# full_board_v1.net
KiCad netlist of a schematic drawn in EAGLE
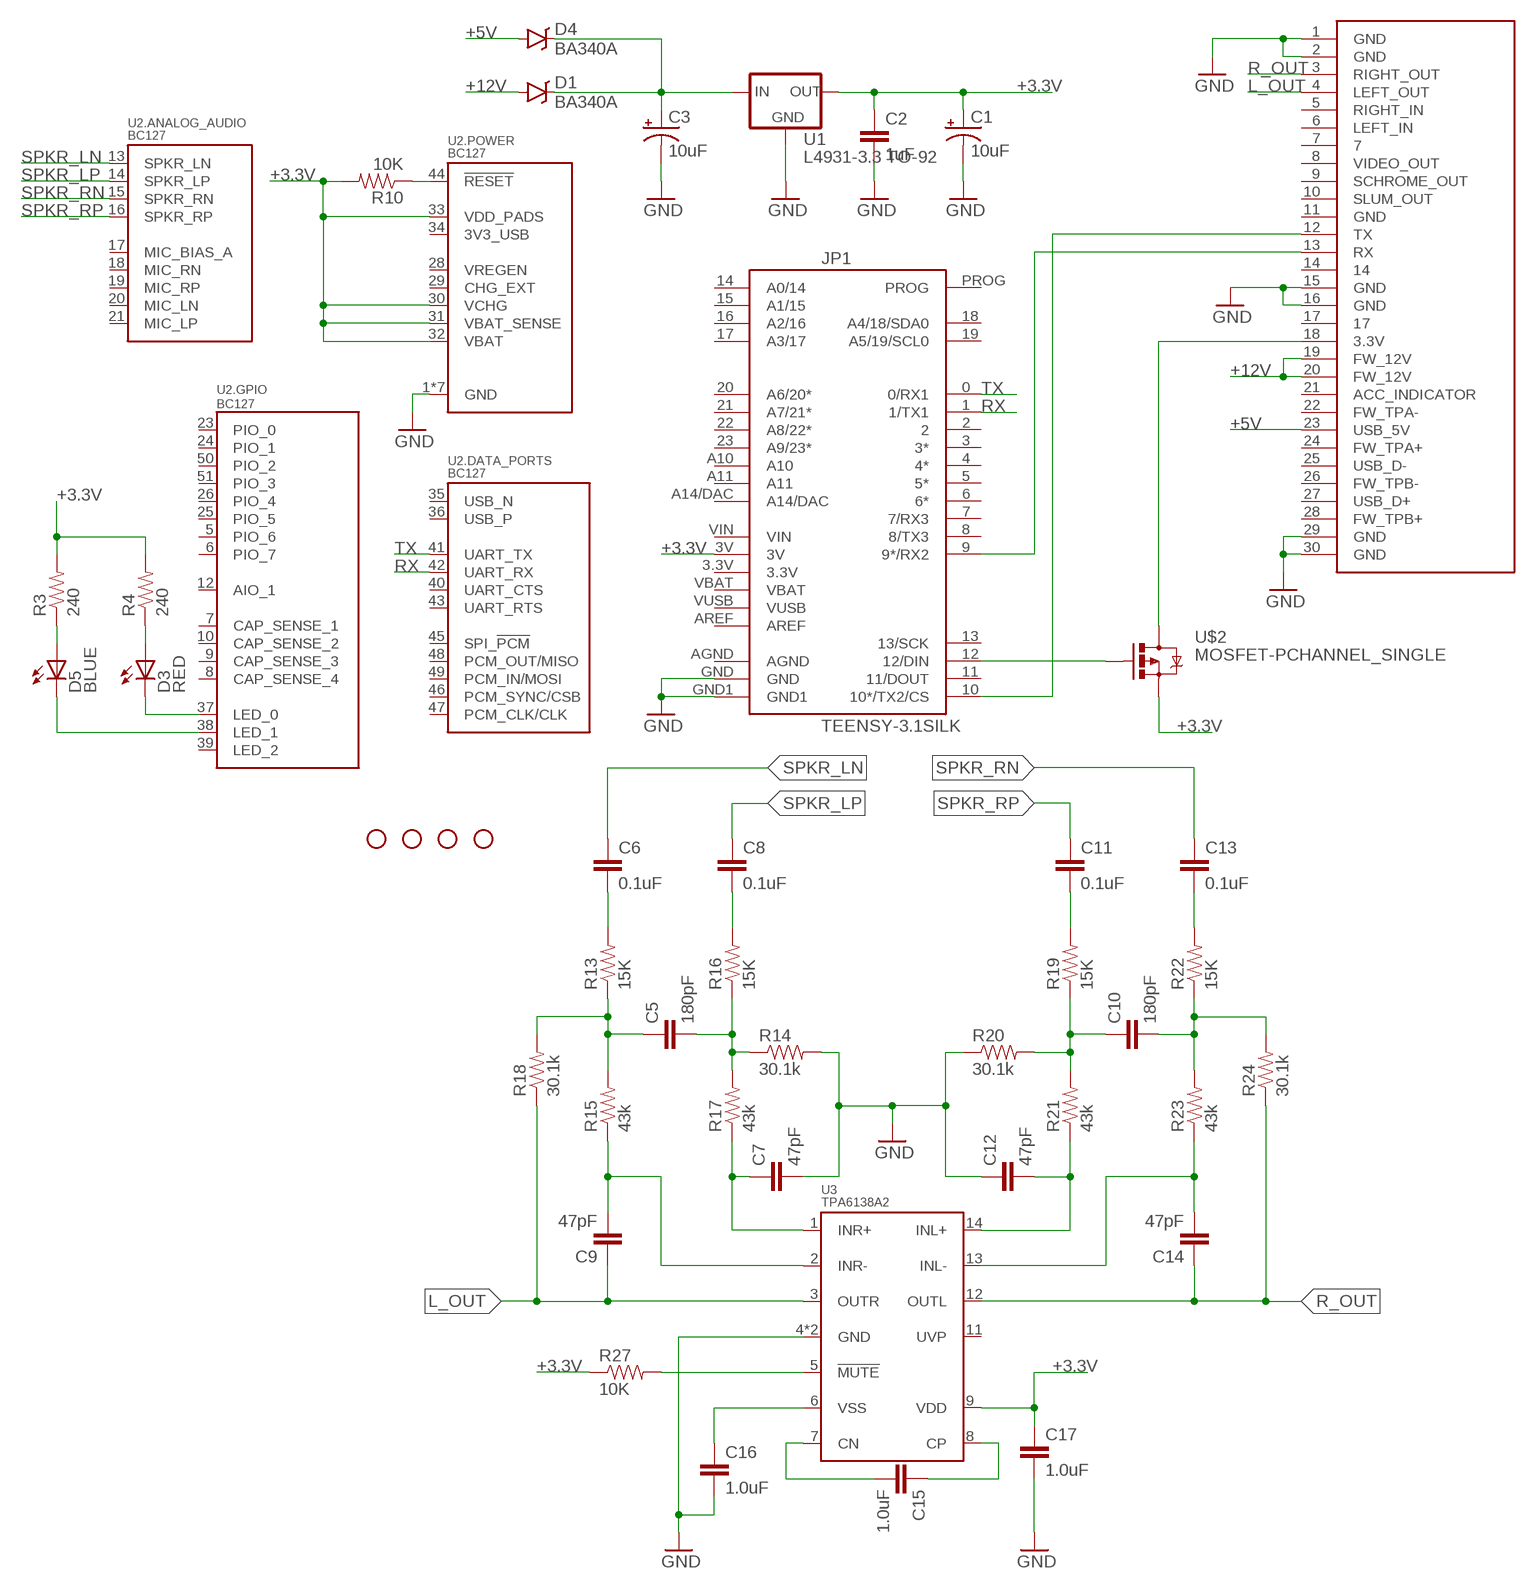
[diagram p0: schematic, sheet 1]

(export (version "E")
  (design (tool "Eeschema 10.0.6"))
  (components
    (comp (ref "C1")
      (value "10uF")
      (footprint "eagle-import:EIA3216")
      (libsource (lib "eagle-import") (part "10UF-16V-10%(TANT)"))
    )
    (comp (ref "C2")
      (value "1uF")
      (footprint "eagle-import:0805")
      (libsource (lib "eagle-import") (part "1UF-25V-10%(0805)"))
    )
    (comp (ref "C3")
      (value "10uF")
      (footprint "eagle-import:EIA3216")
      (libsource (lib "eagle-import") (part "10UF-16V-10%(TANT)"))
    )
    (comp (ref "C5")
      (value "180pF")
      (footprint "eagle-import:0603-CAP")
      (libsource (lib "eagle-import") (part "CAP0603-CAP"))
    )
    (comp (ref "C6")
      (value "0.1uF")
      (footprint "eagle-import:0603-CAP")
      (libsource (lib "eagle-import") (part "0.1UF-25V-5%(0603)"))
    )
    (comp (ref "C7")
      (value "47pF")
      (footprint "eagle-import:0603-CAP")
      (libsource (lib "eagle-import") (part "47PF-50V-5%(0603)"))
    )
    (comp (ref "C8")
      (value "0.1uF")
      (footprint "eagle-import:0603-CAP")
      (libsource (lib "eagle-import") (part "0.1UF-25V-5%(0603)"))
    )
    (comp (ref "C9")
      (value "47pF")
      (footprint "eagle-import:0603-CAP")
      (libsource (lib "eagle-import") (part "47PF-50V-5%(0603)"))
    )
    (comp (ref "C10")
      (value "180pF")
      (footprint "eagle-import:0603-CAP")
      (libsource (lib "eagle-import") (part "CAP0603-CAP"))
    )
    (comp (ref "C11")
      (value "0.1uF")
      (footprint "eagle-import:0603-CAP")
      (libsource (lib "eagle-import") (part "0.1UF-25V-5%(0603)"))
    )
    (comp (ref "C12")
      (value "47pF")
      (footprint "eagle-import:0603-CAP")
      (libsource (lib "eagle-import") (part "47PF-50V-5%(0603)"))
    )
    (comp (ref "C13")
      (value "0.1uF")
      (footprint "eagle-import:0603-CAP")
      (libsource (lib "eagle-import") (part "0.1UF-25V-5%(0603)"))
    )
    (comp (ref "C14")
      (value "47pF")
      (footprint "eagle-import:0603-CAP")
      (libsource (lib "eagle-import") (part "47PF-50V-5%(0603)"))
    )
    (comp (ref "C15")
      (value "1.0uF")
      (footprint "eagle-import:0603-CAP")
      (libsource (lib "eagle-import") (part "1.0UF-16V-10%(0603)"))
    )
    (comp (ref "C16")
      (value "1.0uF")
      (footprint "eagle-import:0603-CAP")
      (libsource (lib "eagle-import") (part "1.0UF-16V-10%(0603)"))
    )
    (comp (ref "C17")
      (value "1.0uF")
      (footprint "eagle-import:0603-CAP")
      (libsource (lib "eagle-import") (part "1.0UF-16V-10%(0603)"))
    )
    (comp (ref "D1")
      (value "BA340A")
      (footprint "eagle-import:SMA-DIODE")
      (libsource (lib "eagle-import") (part "B340A"))
    )
    (comp (ref "D3")
      (value "RED")
      (footprint "eagle-import:LED-0603")
      (libsource (lib "eagle-import") (part "LED-RED0603"))
    )
    (comp (ref "D4")
      (value "BA340A")
      (footprint "eagle-import:SMA-DIODE")
      (libsource (lib "eagle-import") (part "B340A"))
    )
    (comp (ref "D5")
      (value "BLUE")
      (footprint "eagle-import:LED-0603")
      (libsource (lib "eagle-import") (part "LED-BLUE0603"))
    )
    (comp (ref "IPOD_CONNECTOR_FEMALE")
      (value "IPOD_CONNECTOR_FEMALECUTOUT")
      (footprint "eagle-import:IPOD_FEM_SM_CUTOUTS")
      (libsource (lib "eagle-import") (part "IPOD_CONNECTOR_FEMALECUTOUT"))
    )
    (comp (ref "JP1")
      (value "TEENSY-3.1SILK")
      (footprint "eagle-import:TEENSY-3.1")
      (libsource (lib "eagle-import") (part "TEENSY-3.1SILK"))
    )
    (comp (ref "R3")
      (value "240")
      (footprint "eagle-import:0603-RES")
      (libsource (lib "eagle-import") (part "240OHM1/10W1%(0603)"))
    )
    (comp (ref "R4")
      (value "240")
      (footprint "eagle-import:0603-RES")
      (libsource (lib "eagle-import") (part "240OHM1/10W1%(0603)"))
    )
    (comp (ref "R10")
      (value "10K")
      (footprint "eagle-import:0603-RES")
      (libsource (lib "eagle-import") (part "10KOHM1/10W1%(0603)0603"))
    )
    (comp (ref "R13")
      (value "15K")
      (footprint "eagle-import:0603-RES")
      (libsource (lib "eagle-import") (part "15KOHM1/10W1%(0603)0603"))
    )
    (comp (ref "R14")
      (value "30.1k")
      (footprint "eagle-import:0603-RES")
      (libsource (lib "eagle-import") (part "30.1KOHM1/10W1%(0603)"))
    )
    (comp (ref "R15")
      (value "43k")
      (footprint "eagle-import:0603-RES")
      (libsource (lib "eagle-import") (part "43KOHM1/10W1%(0603)"))
    )
    (comp (ref "R16")
      (value "15K")
      (footprint "eagle-import:0603-RES")
      (libsource (lib "eagle-import") (part "15KOHM1/10W1%(0603)0603"))
    )
    (comp (ref "R17")
      (value "43k")
      (footprint "eagle-import:0603-RES")
      (libsource (lib "eagle-import") (part "43KOHM1/10W1%(0603)"))
    )
    (comp (ref "R18")
      (value "30.1k")
      (footprint "eagle-import:0603-RES")
      (libsource (lib "eagle-import") (part "30.1KOHM1/10W1%(0603)"))
    )
    (comp (ref "R19")
      (value "15K")
      (footprint "eagle-import:0603-RES")
      (libsource (lib "eagle-import") (part "15KOHM1/10W1%(0603)0603"))
    )
    (comp (ref "R20")
      (value "30.1k")
      (footprint "eagle-import:0603-RES")
      (libsource (lib "eagle-import") (part "30.1KOHM1/10W1%(0603)"))
    )
    (comp (ref "R21")
      (value "43k")
      (footprint "eagle-import:0603-RES")
      (libsource (lib "eagle-import") (part "43KOHM1/10W1%(0603)"))
    )
    (comp (ref "R22")
      (value "15K")
      (footprint "eagle-import:0603-RES")
      (libsource (lib "eagle-import") (part "15KOHM1/10W1%(0603)0603"))
    )
    (comp (ref "R23")
      (value "43k")
      (footprint "eagle-import:0603-RES")
      (libsource (lib "eagle-import") (part "43KOHM1/10W1%(0603)"))
    )
    (comp (ref "R24")
      (value "30.1k")
      (footprint "eagle-import:0603-RES")
      (libsource (lib "eagle-import") (part "30.1KOHM1/10W1%(0603)"))
    )
    (comp (ref "R27")
      (value "10K")
      (footprint "eagle-import:0603-RES")
      (libsource (lib "eagle-import") (part "10KOHM1/10W1%(0603)0603"))
    )
    (comp (ref "STANDOFF1")
      (value "STAND-OFF")
      (footprint "eagle-import:STAND-OFF")
      (libsource (lib "eagle-import") (part "STAND-OFF"))
    )
    (comp (ref "STANDOFF2")
      (value "STAND-OFF")
      (footprint "eagle-import:STAND-OFF")
      (libsource (lib "eagle-import") (part "STAND-OFF"))
    )
    (comp (ref "STANDOFF3")
      (value "STAND-OFF")
      (footprint "eagle-import:STAND-OFF")
      (libsource (lib "eagle-import") (part "STAND-OFF"))
    )
    (comp (ref "STANDOFF4")
      (value "STAND-OFF")
      (footprint "eagle-import:STAND-OFF")
      (libsource (lib "eagle-import") (part "STAND-OFF"))
    )
    (comp (ref "U$2")
      (value "MOSFET-PCHANNEL_SINGLE")
      (footprint "eagle-import:SOT563-SINGLEFET")
      (libsource (lib "eagle-import") (part "MOSFET-PCHANNEL_SINGLE"))
    )
    (comp (ref "U1")
      (value "L4931-3.3 TO-92")
      (footprint "eagle-import:TO-92")
      (libsource (lib "eagle-import") (part "V_REG_78XXTO-92_UNTESTED"))
    )
    (comp (ref "U2")
      (value "BC127")
      (footprint "eagle-import:BC127_XTRA_PASTE")
      (libsource (lib "eagle-import") (part "BC127EXTRA_PASTE"))
    )
    (comp (ref "U3")
      (value "TPA6138A2")
      (footprint "eagle-import:TSSOP-14")
      (libsource (lib "eagle-import") (part "TPA6138A2"))
    )
  )
  (nets
    (net (code "1") (name "/+3.3V") (class "Default")
      (node (ref "C1") (pin "A") (pinfunction "+_A") (pintype "passive"))
      (node (ref "C17") (pin "1") (pinfunction "1_1") (pintype "passive"))
      (node (ref "C2") (pin "1") (pinfunction "1_1") (pintype "passive"))
      (node (ref "JP1") (pin "3V") (pinfunction "3V_3V") (pintype "bidirectional"))
      (node (ref "R10") (pin "2") (pinfunction "2_2") (pintype "passive"))
      (node (ref "R27") (pin "1") (pinfunction "1_1") (pintype "passive"))
      (node (ref "R3") (pin "2") (pinfunction "2_2") (pintype "passive"))
      (node (ref "R4") (pin "2") (pinfunction "2_2") (pintype "passive"))
      (node (ref "U$2") (pin "S") (pinfunction "S_S") (pintype "passive"))
      (node (ref "U1") (pin "1") (pinfunction "OUT_1") (pintype "passive"))
      (node (ref "U2") (pin "30") (pinfunction "VCHG_30") (pintype "bidirectional"))
      (node (ref "U2") (pin "31") (pinfunction "VBAT_SENSE_31") (pintype "bidirectional"))
      (node (ref "U2") (pin "32") (pinfunction "VBAT_32") (pintype "bidirectional"))
      (node (ref "U2") (pin "33") (pinfunction "VDD_PADS_33") (pintype "bidirectional"))
      (node (ref "U3") (pin "9") (pinfunction "VDD_9") (pintype "bidirectional"))
    )
    (net (code "2") (name "/+5V") (class "Default")
      (node (ref "D4") (pin "A") (pinfunction "A_A") (pintype "passive"))
      (node (ref "IPOD_CONNECTOR_FEMALE") (pin "23") (pinfunction "USB_5V_23") (pintype "bidirectional"))
    )
    (net (code "3") (name "/+12V") (class "Default")
      (node (ref "D1") (pin "A") (pinfunction "A_A") (pintype "passive"))
      (node (ref "IPOD_CONNECTOR_FEMALE") (pin "19") (pinfunction "FW_12V_19") (pintype "bidirectional"))
      (node (ref "IPOD_CONNECTOR_FEMALE") (pin "20") (pinfunction "FW_12V_20") (pintype "bidirectional"))
    )
    (net (code "4") (name "/RX") (class "Default")
      (node (ref "JP1") (pin "1") (pinfunction "1/TX1_1") (pintype "bidirectional"))
      (node (ref "U2") (pin "42") (pinfunction "UART_RX_42") (pintype "bidirectional"))
    )
    (net (code "5") (name "/TX") (class "Default")
      (node (ref "JP1") (pin "0") (pinfunction "0/RX1_0") (pintype "bidirectional"))
      (node (ref "U2") (pin "41") (pinfunction "UART_TX_41") (pintype "bidirectional"))
    )
    (net (code "6") (name "GND") (class "Default")
      (node (ref "C1") (pin "C") (pinfunction "-_C") (pintype "passive"))
      (node (ref "C12") (pin "1") (pinfunction "1_1") (pintype "passive"))
      (node (ref "C16") (pin "2") (pinfunction "2_2") (pintype "passive"))
      (node (ref "C17") (pin "2") (pinfunction "2_2") (pintype "passive"))
      (node (ref "C2") (pin "2") (pinfunction "2_2") (pintype "passive"))
      (node (ref "C3") (pin "C") (pinfunction "-_C") (pintype "passive"))
      (node (ref "C7") (pin "2") (pinfunction "2_2") (pintype "passive"))
      (node (ref "IPOD_CONNECTOR_FEMALE") (pin "1") (pinfunction "GND_1") (pintype "bidirectional"))
      (node (ref "IPOD_CONNECTOR_FEMALE") (pin "15") (pinfunction "GND_15") (pintype "bidirectional"))
      (node (ref "IPOD_CONNECTOR_FEMALE") (pin "16") (pinfunction "GND_16") (pintype "bidirectional"))
      (node (ref "IPOD_CONNECTOR_FEMALE") (pin "2") (pinfunction "GND_2") (pintype "bidirectional"))
      (node (ref "IPOD_CONNECTOR_FEMALE") (pin "29") (pinfunction "GND_29") (pintype "bidirectional"))
      (node (ref "IPOD_CONNECTOR_FEMALE") (pin "30") (pinfunction "GND_30") (pintype "bidirectional"))
      (node (ref "JP1") (pin "GND") (pinfunction "GND_GND") (pintype "bidirectional"))
      (node (ref "JP1") (pin "GND1") (pinfunction "GND1_GND1") (pintype "bidirectional"))
      (node (ref "R14") (pin "2") (pinfunction "2_2") (pintype "passive"))
      (node (ref "R20") (pin "1") (pinfunction "1_1") (pintype "passive"))
      (node (ref "U1") (pin "2") (pinfunction "GND_2") (pintype "input"))
      (node (ref "U2") (pin "1") (pinfunction "GND_1") (pintype "bidirectional"))
      (node (ref "U2") (pin "11") (pinfunction "GND_11") (pintype "bidirectional"))
      (node (ref "U2") (pin "2") (pinfunction "GND_2") (pintype "bidirectional"))
      (node (ref "U2") (pin "22") (pinfunction "GND_22") (pintype "bidirectional"))
      (node (ref "U2") (pin "27") (pinfunction "GND_27") (pintype "bidirectional"))
      (node (ref "U2") (pin "3") (pinfunction "GND_3") (pintype "bidirectional"))
      (node (ref "U2") (pin "4") (pinfunction "GND_4") (pintype "bidirectional"))
      (node (ref "U3") (pin "10") (pinfunction "GND_10") (pintype "bidirectional"))
      (node (ref "U3") (pin "4") (pinfunction "GND_4") (pintype "bidirectional"))
    )
    (net (code "7") (name "L_OUT") (class "Default")
      (node (ref "C9") (pin "1") (pinfunction "1_1") (pintype "passive"))
      (node (ref "IPOD_CONNECTOR_FEMALE") (pin "4") (pinfunction "LEFT_OUT_4") (pintype "bidirectional"))
      (node (ref "R18") (pin "1") (pinfunction "1_1") (pintype "passive"))
      (node (ref "U3") (pin "3") (pinfunction "OUTR_3") (pintype "bidirectional"))
    )
    (net (code "8") (name "Net-(C3-+)") (class "Default")
      (node (ref "C3") (pin "A") (pinfunction "+_A") (pintype "passive"))
      (node (ref "D1") (pin "C") (pinfunction "C_C") (pintype "passive"))
      (node (ref "D4") (pin "C") (pinfunction "C_C") (pintype "passive"))
      (node (ref "U1") (pin "3") (pinfunction "IN_3") (pintype "input"))
    )
    (net (code "9") (name "Net-(C5-Pad1)") (class "Default")
      (node (ref "C5") (pin "1") (pinfunction "1_1") (pintype "passive"))
      (node (ref "R13") (pin "1") (pinfunction "1_1") (pintype "passive"))
      (node (ref "R15") (pin "2") (pinfunction "2_2") (pintype "passive"))
      (node (ref "R18") (pin "2") (pinfunction "2_2") (pintype "passive"))
    )
    (net (code "10") (name "Net-(C5-Pad2)") (class "Default")
      (node (ref "C5") (pin "2") (pinfunction "2_2") (pintype "passive"))
      (node (ref "R14") (pin "1") (pinfunction "1_1") (pintype "passive"))
      (node (ref "R16") (pin "1") (pinfunction "1_1") (pintype "passive"))
      (node (ref "R17") (pin "2") (pinfunction "2_2") (pintype "passive"))
    )
    (net (code "11") (name "Net-(C6-Pad2)") (class "Default")
      (node (ref "C6") (pin "2") (pinfunction "2_2") (pintype "passive"))
      (node (ref "R13") (pin "2") (pinfunction "2_2") (pintype "passive"))
    )
    (net (code "12") (name "Net-(C8-Pad2)") (class "Default")
      (node (ref "C8") (pin "2") (pinfunction "2_2") (pintype "passive"))
      (node (ref "R16") (pin "2") (pinfunction "2_2") (pintype "passive"))
    )
    (net (code "13") (name "Net-(C10-Pad1)") (class "Default")
      (node (ref "C10") (pin "1") (pinfunction "1_1") (pintype "passive"))
      (node (ref "R19") (pin "1") (pinfunction "1_1") (pintype "passive"))
      (node (ref "R20") (pin "2") (pinfunction "2_2") (pintype "passive"))
      (node (ref "R21") (pin "2") (pinfunction "2_2") (pintype "passive"))
    )
    (net (code "14") (name "Net-(C10-Pad2)") (class "Default")
      (node (ref "C10") (pin "2") (pinfunction "2_2") (pintype "passive"))
      (node (ref "R22") (pin "1") (pinfunction "1_1") (pintype "passive"))
      (node (ref "R23") (pin "2") (pinfunction "2_2") (pintype "passive"))
      (node (ref "R24") (pin "2") (pinfunction "2_2") (pintype "passive"))
    )
    (net (code "15") (name "Net-(C11-Pad2)") (class "Default")
      (node (ref "C11") (pin "2") (pinfunction "2_2") (pintype "passive"))
      (node (ref "R19") (pin "2") (pinfunction "2_2") (pintype "passive"))
    )
    (net (code "16") (name "Net-(C13-Pad2)") (class "Default")
      (node (ref "C13") (pin "2") (pinfunction "2_2") (pintype "passive"))
      (node (ref "R22") (pin "2") (pinfunction "2_2") (pintype "passive"))
    )
    (net (code "17") (name "Net-(D3-PadA)") (class "Default")
      (node (ref "D3") (pin "A") (pinfunction "A_A") (pintype "passive"))
      (node (ref "R4") (pin "1") (pinfunction "1_1") (pintype "passive"))
    )
    (net (code "18") (name "Net-(D5-PadA)") (class "Default")
      (node (ref "D5") (pin "A") (pinfunction "A_A") (pintype "passive"))
      (node (ref "R3") (pin "1") (pinfunction "1_1") (pintype "passive"))
    )
    (net (code "19") (name "Net-(IPOD_CONNECTOR_FEMALE-3.3V)") (class "Default")
      (node (ref "IPOD_CONNECTOR_FEMALE") (pin "18") (pinfunction "3.3V_18") (pintype "bidirectional"))
      (node (ref "U$2") (pin "D1") (pinfunction "D_D1") (pintype "passive"))
      (node (ref "U$2") (pin "D2") (pinfunction "D_D2") (pintype "passive"))
      (node (ref "U$2") (pin "D3") (pinfunction "D_D3") (pintype "passive"))
      (node (ref "U$2") (pin "D4") (pinfunction "D_D4") (pintype "passive"))
    )
    (net (code "20") (name "Net-(IPOD_CONNECTOR_FEMALE-RX)") (class "Default")
      (node (ref "IPOD_CONNECTOR_FEMALE") (pin "13") (pinfunction "RX_13") (pintype "bidirectional"))
      (node (ref "JP1") (pin "9") (pinfunction "9*/RX2_9") (pintype "bidirectional"))
    )
    (net (code "21") (name "Net-(IPOD_CONNECTOR_FEMALE-TX)") (class "Default")
      (node (ref "IPOD_CONNECTOR_FEMALE") (pin "12") (pinfunction "TX_12") (pintype "bidirectional"))
      (node (ref "JP1") (pin "10") (pinfunction "10*/TX2/CS_10") (pintype "bidirectional"))
    )
    (net (code "22") (name "Net-(JP1-12{slash}DIN)") (class "Default")
      (node (ref "JP1") (pin "12") (pinfunction "12/DIN_12") (pintype "bidirectional"))
      (node (ref "U$2") (pin "G") (pinfunction "G_G") (pintype "passive"))
    )
    (net (code "23") (name "Net-(U2C-LED_0)") (class "Default")
      (node (ref "D3") (pin "C") (pinfunction "C_C") (pintype "passive"))
      (node (ref "U2") (pin "37") (pinfunction "LED_0_37") (pintype "bidirectional"))
    )
    (net (code "24") (name "Net-(U2C-LED_1)") (class "Default")
      (node (ref "D5") (pin "C") (pinfunction "C_C") (pintype "passive"))
      (node (ref "U2") (pin "38") (pinfunction "LED_1_38") (pintype "bidirectional"))
    )
    (net (code "25") (name "Net-(U2D-~{RESET})") (class "Default")
      (node (ref "R10") (pin "1") (pinfunction "1_1") (pintype "passive"))
      (node (ref "U2") (pin "44") (pinfunction "~{RESET}_44") (pintype "bidirectional"))
    )
    (net (code "26") (name "Net-(U3-CN)") (class "Default")
      (node (ref "C15") (pin "2") (pinfunction "2_2") (pintype "passive"))
      (node (ref "U3") (pin "7") (pinfunction "CN_7") (pintype "bidirectional"))
    )
    (net (code "27") (name "Net-(U3-CP)") (class "Default")
      (node (ref "C15") (pin "1") (pinfunction "1_1") (pintype "passive"))
      (node (ref "U3") (pin "8") (pinfunction "CP_8") (pintype "bidirectional"))
    )
    (net (code "28") (name "Net-(U3-INL+)") (class "Default")
      (node (ref "C12") (pin "2") (pinfunction "2_2") (pintype "passive"))
      (node (ref "R21") (pin "1") (pinfunction "1_1") (pintype "passive"))
      (node (ref "U3") (pin "14") (pinfunction "INL+_14") (pintype "bidirectional"))
    )
    (net (code "29") (name "Net-(U3-INL-)") (class "Default")
      (node (ref "C14") (pin "2") (pinfunction "2_2") (pintype "passive"))
      (node (ref "R23") (pin "1") (pinfunction "1_1") (pintype "passive"))
      (node (ref "U3") (pin "13") (pinfunction "INL-_13") (pintype "bidirectional"))
    )
    (net (code "30") (name "Net-(U3-INR+)") (class "Default")
      (node (ref "C7") (pin "1") (pinfunction "1_1") (pintype "passive"))
      (node (ref "R17") (pin "1") (pinfunction "1_1") (pintype "passive"))
      (node (ref "U3") (pin "1") (pinfunction "INR+_1") (pintype "bidirectional"))
    )
    (net (code "31") (name "Net-(U3-INR-)") (class "Default")
      (node (ref "C9") (pin "2") (pinfunction "2_2") (pintype "passive"))
      (node (ref "R15") (pin "1") (pinfunction "1_1") (pintype "passive"))
      (node (ref "U3") (pin "2") (pinfunction "INR-_2") (pintype "bidirectional"))
    )
    (net (code "32") (name "Net-(U3-VSS)") (class "Default")
      (node (ref "C16") (pin "1") (pinfunction "1_1") (pintype "passive"))
      (node (ref "U3") (pin "6") (pinfunction "VSS_6") (pintype "bidirectional"))
    )
    (net (code "33") (name "Net-(U3-~{MUTE})") (class "Default")
      (node (ref "R27") (pin "2") (pinfunction "2_2") (pintype "passive"))
      (node (ref "U3") (pin "5") (pinfunction "~{MUTE}_5") (pintype "bidirectional"))
    )
    (net (code "34") (name "R_OUT") (class "Default")
      (node (ref "C14") (pin "1") (pinfunction "1_1") (pintype "passive"))
      (node (ref "IPOD_CONNECTOR_FEMALE") (pin "3") (pinfunction "RIGHT_OUT_3") (pintype "bidirectional"))
      (node (ref "R24") (pin "1") (pinfunction "1_1") (pintype "passive"))
      (node (ref "U3") (pin "12") (pinfunction "OUTL_12") (pintype "bidirectional"))
    )
    (net (code "35") (name "SPKR_LN") (class "Default")
      (node (ref "C6") (pin "1") (pinfunction "1_1") (pintype "passive"))
      (node (ref "U2") (pin "13") (pinfunction "SPKR_LN_13") (pintype "bidirectional"))
    )
    (net (code "36") (name "SPKR_LP") (class "Default")
      (node (ref "C8") (pin "1") (pinfunction "1_1") (pintype "passive"))
      (node (ref "U2") (pin "14") (pinfunction "SPKR_LP_14") (pintype "bidirectional"))
    )
    (net (code "37") (name "SPKR_RN") (class "Default")
      (node (ref "C13") (pin "1") (pinfunction "1_1") (pintype "passive"))
      (node (ref "U2") (pin "15") (pinfunction "SPKR_RN_15") (pintype "bidirectional"))
    )
    (net (code "38") (name "SPKR_RP") (class "Default")
      (node (ref "C11") (pin "1") (pinfunction "1_1") (pintype "passive"))
      (node (ref "U2") (pin "16") (pinfunction "SPKR_RP_16") (pintype "bidirectional"))
    )
    (net (code "39") (name "unconnected-(IPOD_CONNECTOR_FEMALE-ACC_INDICATOR-Pad21)") (class "Default")
      (node (ref "IPOD_CONNECTOR_FEMALE") (pin "21") (pinfunction "ACC_INDICATOR_21") (pintype "bidirectional"))
    )
    (net (code "40") (name "unconnected-(IPOD_CONNECTOR_FEMALE-FW_TPA+-Pad24)") (class "Default")
      (node (ref "IPOD_CONNECTOR_FEMALE") (pin "24") (pinfunction "FW_TPA+_24") (pintype "bidirectional"))
    )
    (net (code "41") (name "unconnected-(IPOD_CONNECTOR_FEMALE-FW_TPA--Pad22)") (class "Default")
      (node (ref "IPOD_CONNECTOR_FEMALE") (pin "22") (pinfunction "FW_TPA-_22") (pintype "bidirectional"))
    )
    (net (code "42") (name "unconnected-(IPOD_CONNECTOR_FEMALE-FW_TPB+-Pad28)") (class "Default")
      (node (ref "IPOD_CONNECTOR_FEMALE") (pin "28") (pinfunction "FW_TPB+_28") (pintype "bidirectional"))
    )
    (net (code "43") (name "unconnected-(IPOD_CONNECTOR_FEMALE-FW_TPB--Pad26)") (class "Default")
      (node (ref "IPOD_CONNECTOR_FEMALE") (pin "26") (pinfunction "FW_TPB-_26") (pintype "bidirectional"))
    )
    (net (code "44") (name "unconnected-(IPOD_CONNECTOR_FEMALE-GND-Pad11)") (class "Default")
      (node (ref "IPOD_CONNECTOR_FEMALE") (pin "11") (pinfunction "GND_11") (pintype "bidirectional"))
    )
    (net (code "45") (name "unconnected-(IPOD_CONNECTOR_FEMALE-LEFT_IN-Pad6)") (class "Default")
      (node (ref "IPOD_CONNECTOR_FEMALE") (pin "6") (pinfunction "LEFT_IN_6") (pintype "bidirectional"))
    )
    (net (code "46") (name "unconnected-(IPOD_CONNECTOR_FEMALE-Pad7)") (class "Default")
      (node (ref "IPOD_CONNECTOR_FEMALE") (pin "7") (pinfunction "7_7") (pintype "bidirectional"))
    )
    (net (code "47") (name "unconnected-(IPOD_CONNECTOR_FEMALE-Pad14)") (class "Default")
      (node (ref "IPOD_CONNECTOR_FEMALE") (pin "14") (pinfunction "14_14") (pintype "bidirectional"))
    )
    (net (code "48") (name "unconnected-(IPOD_CONNECTOR_FEMALE-Pad17)") (class "Default")
      (node (ref "IPOD_CONNECTOR_FEMALE") (pin "17") (pinfunction "17_17") (pintype "bidirectional"))
    )
    (net (code "49") (name "unconnected-(IPOD_CONNECTOR_FEMALE-RIGHT_IN-Pad5)") (class "Default")
      (node (ref "IPOD_CONNECTOR_FEMALE") (pin "5") (pinfunction "RIGHT_IN_5") (pintype "bidirectional"))
    )
    (net (code "50") (name "unconnected-(IPOD_CONNECTOR_FEMALE-SCHROME_OUT-Pad9)") (class "Default")
      (node (ref "IPOD_CONNECTOR_FEMALE") (pin "9") (pinfunction "SCHROME_OUT_9") (pintype "bidirectional"))
    )
    (net (code "51") (name "unconnected-(IPOD_CONNECTOR_FEMALE-SLUM_OUT-Pad10)") (class "Default")
      (node (ref "IPOD_CONNECTOR_FEMALE") (pin "10") (pinfunction "SLUM_OUT_10") (pintype "bidirectional"))
    )
    (net (code "52") (name "unconnected-(IPOD_CONNECTOR_FEMALE-USB_D+-Pad27)") (class "Default")
      (node (ref "IPOD_CONNECTOR_FEMALE") (pin "27") (pinfunction "USB_D+_27") (pintype "bidirectional"))
    )
    (net (code "53") (name "unconnected-(IPOD_CONNECTOR_FEMALE-USB_D--Pad25)") (class "Default")
      (node (ref "IPOD_CONNECTOR_FEMALE") (pin "25") (pinfunction "USB_D-_25") (pintype "bidirectional"))
    )
    (net (code "54") (name "unconnected-(IPOD_CONNECTOR_FEMALE-VIDEO_OUT-Pad8)") (class "Default")
      (node (ref "IPOD_CONNECTOR_FEMALE") (pin "8") (pinfunction "VIDEO_OUT_8") (pintype "bidirectional"))
    )
    (net (code "55") (name "unconnected-(JP1-3*-Pad3)") (class "Default")
      (node (ref "JP1") (pin "3") (pinfunction "3*_3") (pintype "bidirectional"))
    )
    (net (code "56") (name "unconnected-(JP1-4*-Pad4)") (class "Default")
      (node (ref "JP1") (pin "4") (pinfunction "4*_4") (pintype "bidirectional"))
    )
    (net (code "57") (name "unconnected-(JP1-5*-Pad5)") (class "Default")
      (node (ref "JP1") (pin "5") (pinfunction "5*_5") (pintype "bidirectional"))
    )
    (net (code "58") (name "unconnected-(JP1-6*-Pad6)") (class "Default")
      (node (ref "JP1") (pin "6") (pinfunction "6*_6") (pintype "bidirectional"))
    )
    (net (code "59") (name "unconnected-(JP1-7{slash}RX3-Pad7)") (class "Default")
      (node (ref "JP1") (pin "7") (pinfunction "7/RX3_7") (pintype "bidirectional"))
    )
    (net (code "60") (name "unconnected-(JP1-8{slash}TX3-Pad8)") (class "Default")
      (node (ref "JP1") (pin "8") (pinfunction "8/TX3_8") (pintype "bidirectional"))
    )
    (net (code "61") (name "unconnected-(JP1-11{slash}DOUT-Pad11)") (class "Default")
      (node (ref "JP1") (pin "11") (pinfunction "11/DOUT_11") (pintype "bidirectional"))
    )
    (net (code "62") (name "unconnected-(JP1-13{slash}SCK-Pad13)") (class "Default")
      (node (ref "JP1") (pin "13") (pinfunction "13/SCK_13") (pintype "bidirectional"))
    )
    (net (code "63") (name "unconnected-(JP1-A0{slash}14-Pad14)") (class "Default")
      (node (ref "JP1") (pin "14") (pinfunction "A0/14_14") (pintype "bidirectional"))
    )
    (net (code "64") (name "unconnected-(JP1-A1{slash}15-Pad15)") (class "Default")
      (node (ref "JP1") (pin "15") (pinfunction "A1/15_15") (pintype "bidirectional"))
    )
    (net (code "65") (name "unconnected-(JP1-A2{slash}16-Pad16)") (class "Default")
      (node (ref "JP1") (pin "16") (pinfunction "A2/16_16") (pintype "bidirectional"))
    )
    (net (code "66") (name "unconnected-(JP1-A3{slash}17-Pad17)") (class "Default")
      (node (ref "JP1") (pin "17") (pinfunction "A3/17_17") (pintype "bidirectional"))
    )
    (net (code "67") (name "unconnected-(JP1-A4{slash}18{slash}SDA0-Pad18)") (class "Default")
      (node (ref "JP1") (pin "18") (pinfunction "A4/18/SDA0_18") (pintype "bidirectional"))
    )
    (net (code "68") (name "unconnected-(JP1-A5{slash}19{slash}SCL0-Pad19)") (class "Default")
      (node (ref "JP1") (pin "19") (pinfunction "A5/19/SCL0_19") (pintype "bidirectional"))
    )
    (net (code "69") (name "unconnected-(JP1-A6{slash}20*-Pad20)") (class "Default")
      (node (ref "JP1") (pin "20") (pinfunction "A6/20*_20") (pintype "bidirectional"))
    )
    (net (code "70") (name "unconnected-(JP1-A7{slash}21*-Pad21)") (class "Default")
      (node (ref "JP1") (pin "21") (pinfunction "A7/21*_21") (pintype "bidirectional"))
    )
    (net (code "71") (name "unconnected-(JP1-A8{slash}22*-Pad22)") (class "Default")
      (node (ref "JP1") (pin "22") (pinfunction "A8/22*_22") (pintype "bidirectional"))
    )
    (net (code "72") (name "unconnected-(JP1-A9{slash}23*-Pad23)") (class "Default")
      (node (ref "JP1") (pin "23") (pinfunction "A9/23*_23") (pintype "bidirectional"))
    )
    (net (code "73") (name "unconnected-(JP1-Pad2)") (class "Default")
      (node (ref "JP1") (pin "2") (pinfunction "2_2") (pintype "bidirectional"))
    )
    (net (code "74") (name "unconnected-(JP1-Pad3.3V)") (class "Default")
      (node (ref "JP1") (pin "3.3V") (pinfunction "3.3V_3.3V") (pintype "bidirectional"))
    )
    (net (code "75") (name "unconnected-(JP1-PadA10)") (class "Default")
      (node (ref "JP1") (pin "A10") (pinfunction "A10_A10") (pintype "bidirectional"))
    )
    (net (code "76") (name "unconnected-(JP1-PadA11)") (class "Default")
      (node (ref "JP1") (pin "A11") (pinfunction "A11_A11") (pintype "bidirectional"))
    )
    (net (code "77") (name "unconnected-(JP1-PadA14{slash}DAC)") (class "Default")
      (node (ref "JP1") (pin "A14/DAC") (pinfunction "A14/DAC_A14/DAC") (pintype "bidirectional"))
    )
    (net (code "78") (name "unconnected-(JP1-PadAGND)") (class "Default")
      (node (ref "JP1") (pin "AGND") (pinfunction "AGND_AGND") (pintype "bidirectional"))
    )
    (net (code "79") (name "unconnected-(JP1-PadAREF)") (class "Default")
      (node (ref "JP1") (pin "AREF") (pinfunction "AREF_AREF") (pintype "bidirectional"))
    )
    (net (code "80") (name "unconnected-(JP1-PadPROG)") (class "Default")
      (node (ref "JP1") (pin "PROG") (pinfunction "PROG_PROG") (pintype "bidirectional"))
    )
    (net (code "81") (name "unconnected-(JP1-PadVBAT)") (class "Default")
      (node (ref "JP1") (pin "VBAT") (pinfunction "VBAT_VBAT") (pintype "bidirectional"))
    )
    (net (code "82") (name "unconnected-(JP1-PadVIN)") (class "Default")
      (node (ref "JP1") (pin "VIN") (pinfunction "VIN_VIN") (pintype "bidirectional"))
    )
    (net (code "83") (name "unconnected-(JP1-PadVUSB)") (class "Default")
      (node (ref "JP1") (pin "VUSB") (pinfunction "VUSB_VUSB") (pintype "bidirectional"))
    )
    (net (code "84") (name "unconnected-(U2A-MIC_BIAS_A-Pad17)") (class "Default")
      (node (ref "U2") (pin "17") (pinfunction "MIC_BIAS_A_17") (pintype "bidirectional"))
    )
    (net (code "85") (name "unconnected-(U2A-MIC_LN-Pad20)") (class "Default")
      (node (ref "U2") (pin "20") (pinfunction "MIC_LN_20") (pintype "bidirectional"))
    )
    (net (code "86") (name "unconnected-(U2A-MIC_LP-Pad21)") (class "Default")
      (node (ref "U2") (pin "21") (pinfunction "MIC_LP_21") (pintype "bidirectional"))
    )
    (net (code "87") (name "unconnected-(U2A-MIC_RN-Pad18)") (class "Default")
      (node (ref "U2") (pin "18") (pinfunction "MIC_RN_18") (pintype "bidirectional"))
    )
    (net (code "88") (name "unconnected-(U2A-MIC_RP-Pad19)") (class "Default")
      (node (ref "U2") (pin "19") (pinfunction "MIC_RP_19") (pintype "bidirectional"))
    )
    (net (code "89") (name "unconnected-(U2B-PCM_CLK{slash}CLK-Pad47)") (class "Default")
      (node (ref "U2") (pin "47") (pinfunction "PCM_CLK/CLK_47") (pintype "bidirectional"))
    )
    (net (code "90") (name "unconnected-(U2B-PCM_IN{slash}MOSI-Pad49)") (class "Default")
      (node (ref "U2") (pin "49") (pinfunction "PCM_IN/MOSI_49") (pintype "bidirectional"))
    )
    (net (code "91") (name "unconnected-(U2B-PCM_OUT{slash}MISO-Pad48)") (class "Default")
      (node (ref "U2") (pin "48") (pinfunction "PCM_OUT/MISO_48") (pintype "bidirectional"))
    )
    (net (code "92") (name "unconnected-(U2B-PCM_SYNC{slash}CSB-Pad46)") (class "Default")
      (node (ref "U2") (pin "46") (pinfunction "PCM_SYNC/CSB_46") (pintype "bidirectional"))
    )
    (net (code "93") (name "unconnected-(U2B-SPI_~{PCM}-Pad45)") (class "Default")
      (node (ref "U2") (pin "45") (pinfunction "SPI_~{PCM}_45") (pintype "bidirectional"))
    )
    (net (code "94") (name "unconnected-(U2B-UART_CTS-Pad40)") (class "Default")
      (node (ref "U2") (pin "40") (pinfunction "UART_CTS_40") (pintype "bidirectional"))
    )
    (net (code "95") (name "unconnected-(U2B-UART_RTS-Pad43)") (class "Default")
      (node (ref "U2") (pin "43") (pinfunction "UART_RTS_43") (pintype "bidirectional"))
    )
    (net (code "96") (name "unconnected-(U2B-USB_N-Pad35)") (class "Default")
      (node (ref "U2") (pin "35") (pinfunction "USB_N_35") (pintype "bidirectional"))
    )
    (net (code "97") (name "unconnected-(U2B-USB_P-Pad36)") (class "Default")
      (node (ref "U2") (pin "36") (pinfunction "USB_P_36") (pintype "bidirectional"))
    )
    (net (code "98") (name "unconnected-(U2C-AIO_1-Pad12)") (class "Default")
      (node (ref "U2") (pin "12") (pinfunction "AIO_1_12") (pintype "bidirectional"))
    )
    (net (code "99") (name "unconnected-(U2C-CAP_SENSE_1-Pad7)") (class "Default")
      (node (ref "U2") (pin "7") (pinfunction "CAP_SENSE_1_7") (pintype "bidirectional"))
    )
    (net (code "100") (name "unconnected-(U2C-CAP_SENSE_2-Pad10)") (class "Default")
      (node (ref "U2") (pin "10") (pinfunction "CAP_SENSE_2_10") (pintype "bidirectional"))
    )
    (net (code "101") (name "unconnected-(U2C-CAP_SENSE_3-Pad9)") (class "Default")
      (node (ref "U2") (pin "9") (pinfunction "CAP_SENSE_3_9") (pintype "bidirectional"))
    )
    (net (code "102") (name "unconnected-(U2C-CAP_SENSE_4-Pad8)") (class "Default")
      (node (ref "U2") (pin "8") (pinfunction "CAP_SENSE_4_8") (pintype "bidirectional"))
    )
    (net (code "103") (name "unconnected-(U2C-LED_2-Pad39)") (class "Default")
      (node (ref "U2") (pin "39") (pinfunction "LED_2_39") (pintype "bidirectional"))
    )
    (net (code "104") (name "unconnected-(U2C-PIO_0-Pad23)") (class "Default")
      (node (ref "U2") (pin "23") (pinfunction "PIO_0_23") (pintype "bidirectional"))
    )
    (net (code "105") (name "unconnected-(U2C-PIO_1-Pad24)") (class "Default")
      (node (ref "U2") (pin "24") (pinfunction "PIO_1_24") (pintype "bidirectional"))
    )
    (net (code "106") (name "unconnected-(U2C-PIO_2-Pad50)") (class "Default")
      (node (ref "U2") (pin "50") (pinfunction "PIO_2_50") (pintype "bidirectional"))
    )
    (net (code "107") (name "unconnected-(U2C-PIO_3-Pad51)") (class "Default")
      (node (ref "U2") (pin "51") (pinfunction "PIO_3_51") (pintype "bidirectional"))
    )
    (net (code "108") (name "unconnected-(U2C-PIO_4-Pad26)") (class "Default")
      (node (ref "U2") (pin "26") (pinfunction "PIO_4_26") (pintype "bidirectional"))
    )
    (net (code "109") (name "unconnected-(U2C-PIO_5-Pad25)") (class "Default")
      (node (ref "U2") (pin "25") (pinfunction "PIO_5_25") (pintype "bidirectional"))
    )
    (net (code "110") (name "unconnected-(U2C-PIO_6-Pad5)") (class "Default")
      (node (ref "U2") (pin "5") (pinfunction "PIO_6_5") (pintype "bidirectional"))
    )
    (net (code "111") (name "unconnected-(U2C-PIO_7-Pad6)") (class "Default")
      (node (ref "U2") (pin "6") (pinfunction "PIO_7_6") (pintype "bidirectional"))
    )
    (net (code "112") (name "unconnected-(U2D-3V3_USB-Pad34)") (class "Default")
      (node (ref "U2") (pin "34") (pinfunction "3V3_USB_34") (pintype "bidirectional"))
    )
    (net (code "113") (name "unconnected-(U2D-CHG_EXT-Pad29)") (class "Default")
      (node (ref "U2") (pin "29") (pinfunction "CHG_EXT_29") (pintype "bidirectional"))
    )
    (net (code "114") (name "unconnected-(U2D-VREGEN-Pad28)") (class "Default")
      (node (ref "U2") (pin "28") (pinfunction "VREGEN_28") (pintype "bidirectional"))
    )
    (net (code "115") (name "unconnected-(U3-UVP-Pad11)") (class "Default")
      (node (ref "U3") (pin "11") (pinfunction "UVP_11") (pintype "bidirectional"))
    )
  )
)
